# 8_output_sense_mux_half.net
KiCad netlist of a schematic drawn in EAGLE
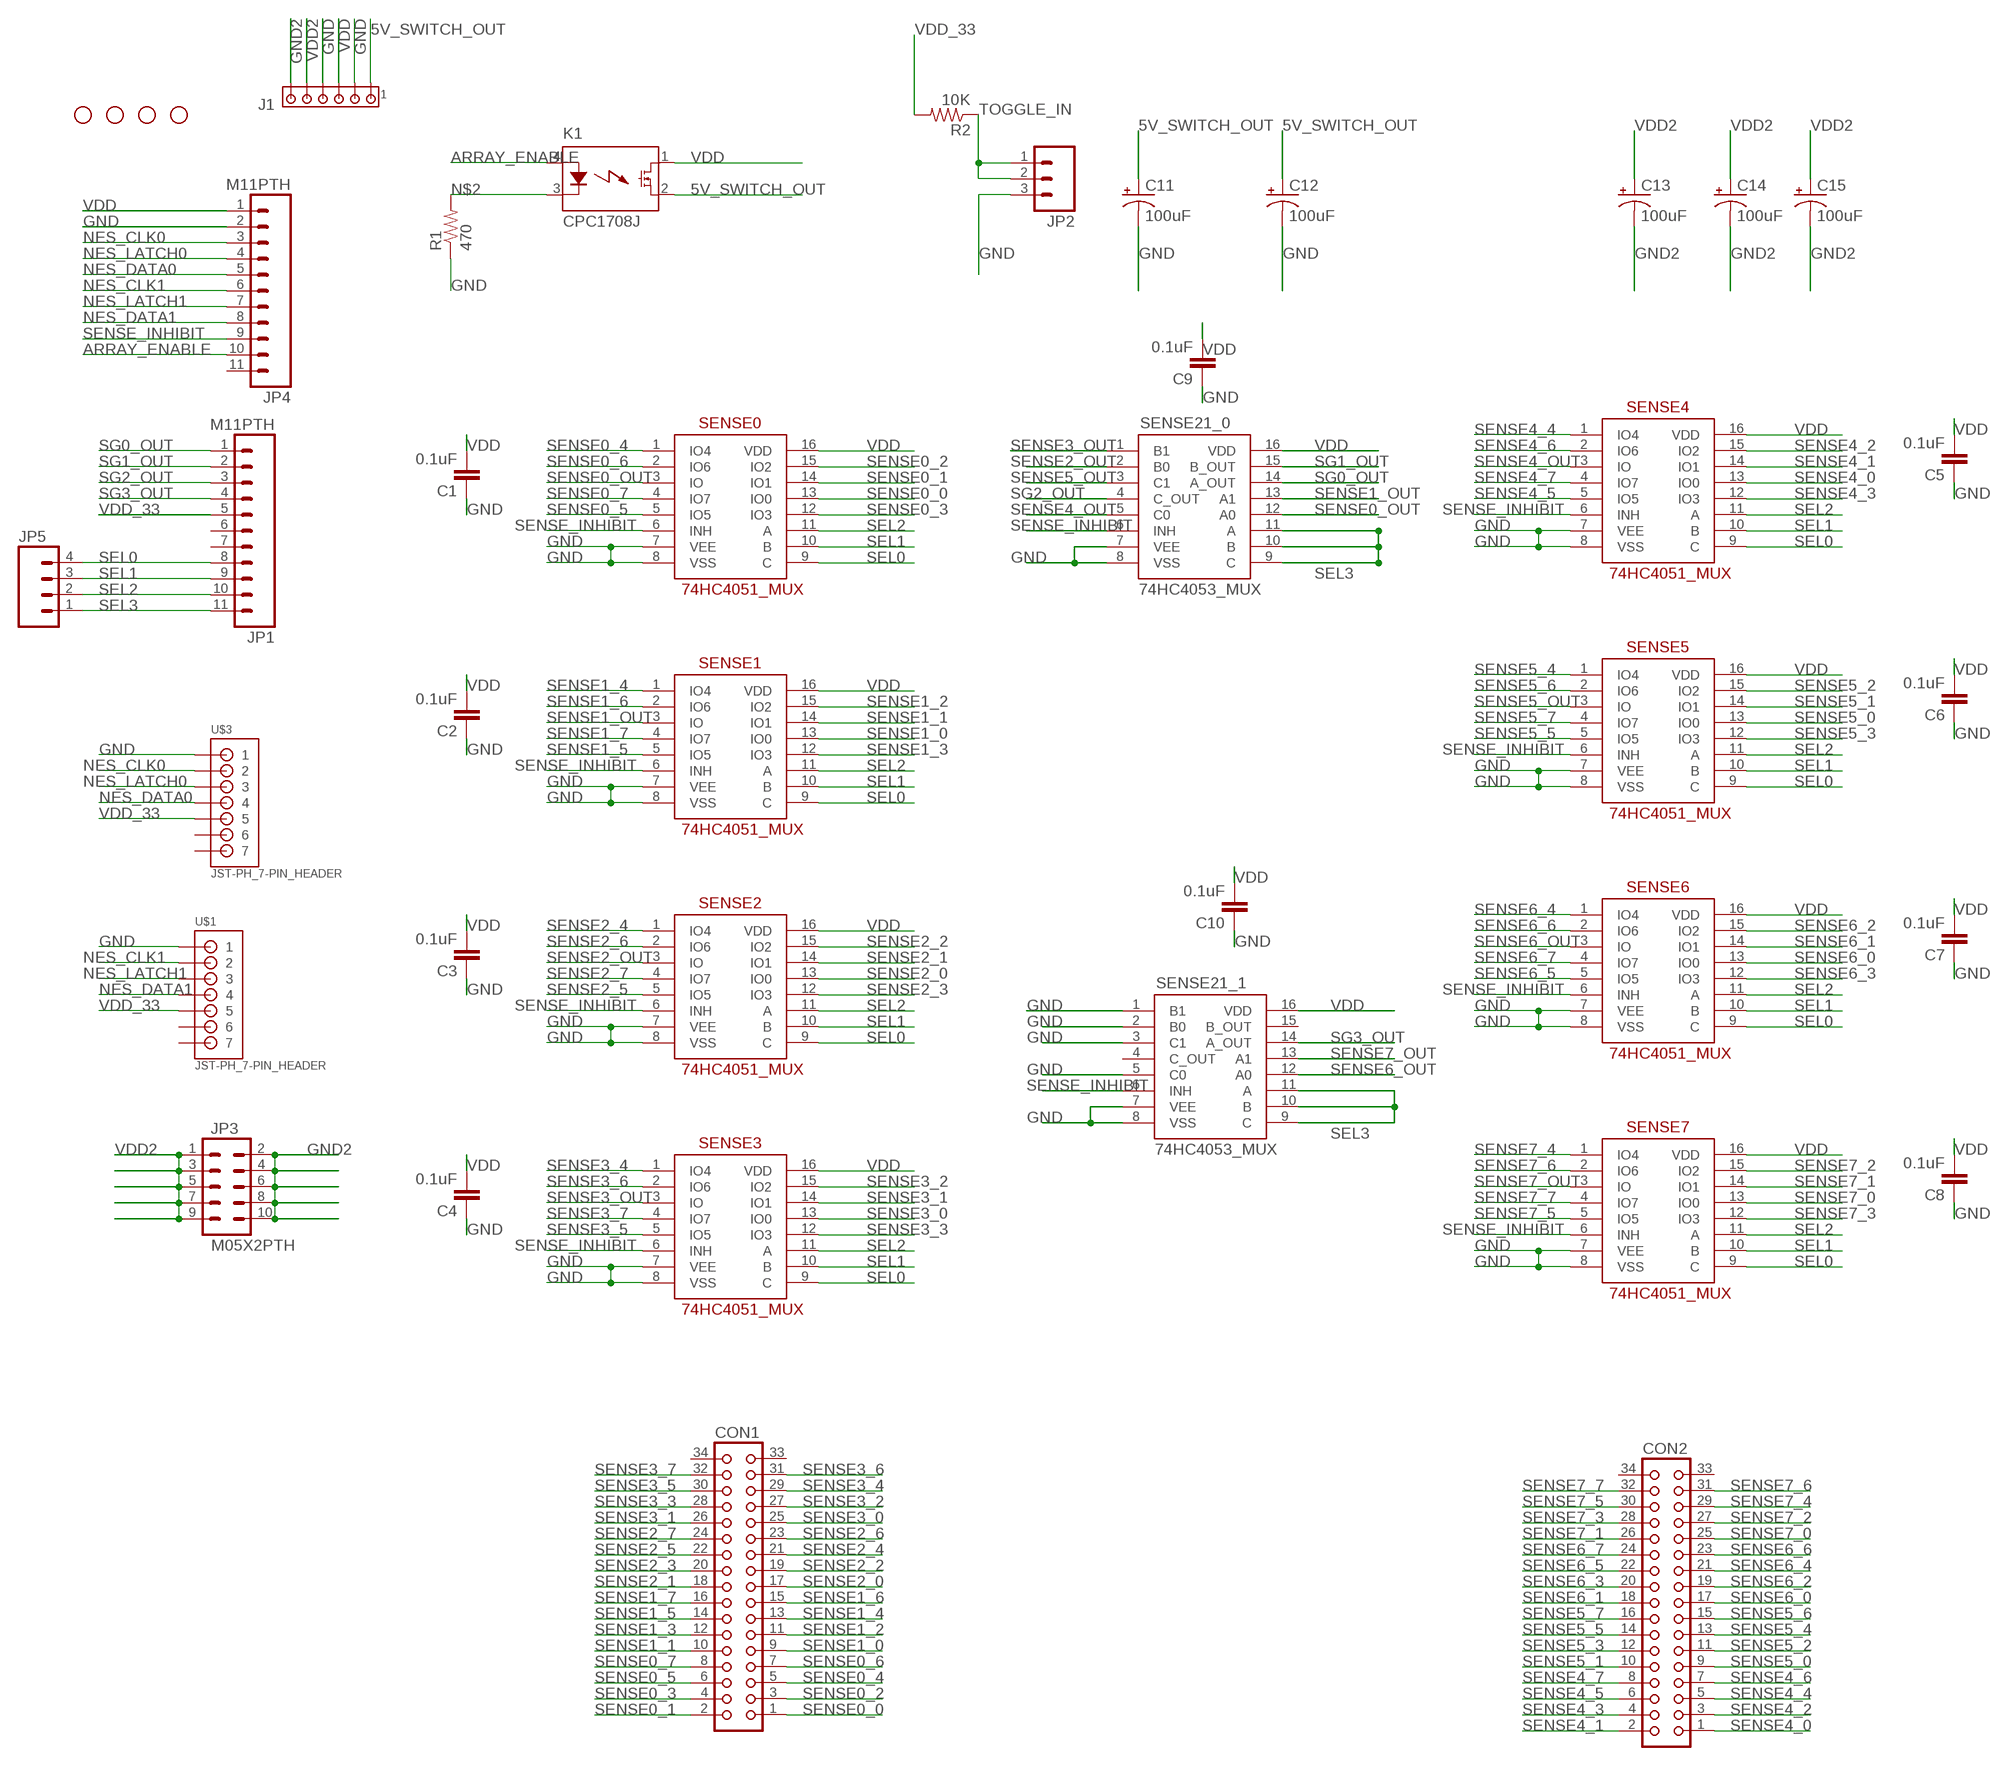
[diagram p0: schematic, sheet 1]

(export (version "E")
  (design (tool "Eeschema 10.0.6"))
  (components
    (comp (ref "C1")
      (value "0.1uF")
      (footprint "eagle-import:C2.5-3")
      (libsource (lib "eagle-import") (part "C2,5-3"))
    )
    (comp (ref "C2")
      (value "0.1uF")
      (footprint "eagle-import:C2.5-3")
      (libsource (lib "eagle-import") (part "C2,5-3"))
    )
    (comp (ref "C3")
      (value "0.1uF")
      (footprint "eagle-import:C2.5-3")
      (libsource (lib "eagle-import") (part "C2,5-3"))
    )
    (comp (ref "C4")
      (value "0.1uF")
      (footprint "eagle-import:C2.5-3")
      (libsource (lib "eagle-import") (part "C2,5-3"))
    )
    (comp (ref "C5")
      (value "0.1uF")
      (footprint "eagle-import:C2.5-3")
      (libsource (lib "eagle-import") (part "C2,5-3"))
    )
    (comp (ref "C6")
      (value "0.1uF")
      (footprint "eagle-import:C2.5-3")
      (libsource (lib "eagle-import") (part "C2,5-3"))
    )
    (comp (ref "C7")
      (value "0.1uF")
      (footprint "eagle-import:C2.5-3")
      (libsource (lib "eagle-import") (part "C2,5-3"))
    )
    (comp (ref "C8")
      (value "0.1uF")
      (footprint "eagle-import:C2.5-3")
      (libsource (lib "eagle-import") (part "C2,5-3"))
    )
    (comp (ref "C9")
      (value "0.1uF")
      (footprint "eagle-import:C2.5-3")
      (libsource (lib "eagle-import") (part "C2,5-3"))
    )
    (comp (ref "C10")
      (value "0.1uF")
      (footprint "eagle-import:C2.5-3")
      (libsource (lib "eagle-import") (part "C2,5-3"))
    )
    (comp (ref "C11")
      (value "100uF")
      (footprint "eagle-import:CPOL-RADIAL-100UF-25V")
      (libsource (lib "eagle-import") (part "CAP_POLPTH1"))
    )
    (comp (ref "C12")
      (value "100uF")
      (footprint "eagle-import:CPOL-RADIAL-100UF-25V")
      (libsource (lib "eagle-import") (part "CAP_POLPTH1"))
    )
    (comp (ref "C13")
      (value "100uF")
      (footprint "eagle-import:CPOL-RADIAL-100UF-25V")
      (libsource (lib "eagle-import") (part "CAP_POLPTH1"))
    )
    (comp (ref "C14")
      (value "100uF")
      (footprint "eagle-import:CPOL-RADIAL-100UF-25V")
      (libsource (lib "eagle-import") (part "CAP_POLPTH1"))
    )
    (comp (ref "C15")
      (value "100uF")
      (footprint "eagle-import:CPOL-RADIAL-100UF-25V")
      (libsource (lib "eagle-import") (part "CAP_POLPTH1"))
    )
    (comp (ref "CON1")
      (value "CON34")
      (footprint "eagle-import:CON34")
      (libsource (lib "eagle-import") (part "CON34"))
    )
    (comp (ref "CON2")
      (value "CON34")
      (footprint "eagle-import:CON34")
      (libsource (lib "eagle-import") (part "CON34"))
    )
    (comp (ref "J1")
      (value "MTA06-156")
      (footprint "eagle-import:1X6MTA")
      (libsource (lib "eagle-import") (part "MTA06-156"))
    )
    (comp (ref "JP1")
      (value "M11PTH")
      (footprint "eagle-import:1X11")
      (libsource (lib "eagle-import") (part "M11PTH"))
    )
    (comp (ref "JP2")
      (value "M03PTH")
      (footprint "eagle-import:1X03")
      (libsource (lib "eagle-import") (part "M03PTH"))
    )
    (comp (ref "JP3")
      (value "M05X2PTH")
      (footprint "eagle-import:AVR_ICSP")
      (libsource (lib "eagle-import") (part "M05X2PTH"))
    )
    (comp (ref "JP4")
      (value "M11PTH")
      (footprint "eagle-import:1X11")
      (libsource (lib "eagle-import") (part "M11PTH"))
    )
    (comp (ref "JP5")
      (value "M04PTH")
      (footprint "eagle-import:1X04")
      (libsource (lib "eagle-import") (part "M04PTH"))
    )
    (comp (ref "K1")
      (value "CPC1708J")
      (footprint "eagle-import:I4-PAC")
      (libsource (lib "eagle-import") (part "CPC1708J"))
    )
    (comp (ref "R1")
      (value "470")
      (footprint "eagle-import:AXIAL-0.3-KIT")
      (libsource (lib "eagle-import") (part "10KOHM1/6W5%(PTH)KIT"))
    )
    (comp (ref "R2")
      (value "10K")
      (footprint "eagle-import:AXIAL-0.3-KIT")
      (libsource (lib "eagle-import") (part "10KOHM1/6W5%(PTH)KIT"))
    )
    (comp (ref "SENSE0")
      (value "74HC4051_MUX")
      (footprint "eagle-import:DIL16")
      (libsource (lib "eagle-import") (part "74HC4051_MUX"))
    )
    (comp (ref "SENSE1")
      (value "74HC4051_MUX")
      (footprint "eagle-import:DIL16")
      (libsource (lib "eagle-import") (part "74HC4051_MUX"))
    )
    (comp (ref "SENSE2")
      (value "74HC4051_MUX")
      (footprint "eagle-import:DIL16")
      (libsource (lib "eagle-import") (part "74HC4051_MUX"))
    )
    (comp (ref "SENSE3")
      (value "74HC4051_MUX")
      (footprint "eagle-import:DIL16")
      (libsource (lib "eagle-import") (part "74HC4051_MUX"))
    )
    (comp (ref "SENSE4")
      (value "74HC4051_MUX")
      (footprint "eagle-import:DIL16")
      (libsource (lib "eagle-import") (part "74HC4051_MUX"))
    )
    (comp (ref "SENSE5")
      (value "74HC4051_MUX")
      (footprint "eagle-import:DIL16")
      (libsource (lib "eagle-import") (part "74HC4051_MUX"))
    )
    (comp (ref "SENSE6")
      (value "74HC4051_MUX")
      (footprint "eagle-import:DIL16")
      (libsource (lib "eagle-import") (part "74HC4051_MUX"))
    )
    (comp (ref "SENSE7")
      (value "74HC4051_MUX")
      (footprint "eagle-import:DIL16")
      (libsource (lib "eagle-import") (part "74HC4051_MUX"))
    )
    (comp (ref "SENSE21_0")
      (value "74HC4053_MUX")
      (footprint "eagle-import:DIL16")
      (libsource (lib "eagle-import") (part "74HC4053_MUX"))
    )
    (comp (ref "SENSE21_1")
      (value "74HC4053_MUX")
      (footprint "eagle-import:DIL16")
      (libsource (lib "eagle-import") (part "74HC4053_MUX"))
    )
    (comp (ref "STANDOFF1")
      (value "STAND-OFF")
      (footprint "eagle-import:STAND-OFF")
      (libsource (lib "eagle-import") (part "STAND-OFF"))
    )
    (comp (ref "STANDOFF2")
      (value "STAND-OFF")
      (footprint "eagle-import:STAND-OFF")
      (libsource (lib "eagle-import") (part "STAND-OFF"))
    )
    (comp (ref "STANDOFF3")
      (value "STAND-OFF")
      (footprint "eagle-import:STAND-OFF")
      (libsource (lib "eagle-import") (part "STAND-OFF"))
    )
    (comp (ref "STANDOFF4")
      (value "STAND-OFF")
      (footprint "eagle-import:STAND-OFF")
      (libsource (lib "eagle-import") (part "STAND-OFF"))
    )
    (comp (ref "U$1")
      (value "JST-PH_7-PIN_HEADER")
      (footprint "eagle-import:JST_B7B-PH_HEADER")
      (libsource (lib "eagle-import") (part "JST-PH_7-PIN_HEADER"))
    )
    (comp (ref "U$3")
      (value "JST-PH_7-PIN_HEADER")
      (footprint "eagle-import:JST_B7B-PH_HEADER")
      (libsource (lib "eagle-import") (part "JST-PH_7-PIN_HEADER"))
    )
  )
  (nets
    (net (code "1") (name "/5V_SWITCH_OUT") (class "Default")
      (node (ref "C11") (pin "1") (pinfunction "+_1") (pintype "passive"))
      (node (ref "C12") (pin "1") (pinfunction "+_1") (pintype "passive"))
      (node (ref "J1") (pin "1") (pinfunction "1_1") (pintype "passive"))
      (node (ref "K1") (pin "2") (pinfunction "DS2_2") (pintype "passive"))
    )
    (net (code "2") (name "/ARRAY_ENABLE") (class "Default")
      (node (ref "JP4") (pin "10") (pinfunction "10_10") (pintype "passive"))
      (node (ref "K1") (pin "4") (pinfunction "A_4") (pintype "passive"))
    )
    (net (code "3") (name "/GND") (class "Default")
      (node (ref "C1") (pin "1") (pinfunction "1_1") (pintype "passive"))
      (node (ref "C10") (pin "1") (pinfunction "1_1") (pintype "passive"))
      (node (ref "C11") (pin "2") (pinfunction "-_2") (pintype "passive"))
      (node (ref "C12") (pin "2") (pinfunction "-_2") (pintype "passive"))
      (node (ref "C2") (pin "1") (pinfunction "1_1") (pintype "passive"))
      (node (ref "C3") (pin "1") (pinfunction "1_1") (pintype "passive"))
      (node (ref "C4") (pin "1") (pinfunction "1_1") (pintype "passive"))
      (node (ref "C5") (pin "1") (pinfunction "1_1") (pintype "passive"))
      (node (ref "C6") (pin "1") (pinfunction "1_1") (pintype "passive"))
      (node (ref "C7") (pin "1") (pinfunction "1_1") (pintype "passive"))
      (node (ref "C8") (pin "1") (pinfunction "1_1") (pintype "passive"))
      (node (ref "C9") (pin "1") (pinfunction "1_1") (pintype "passive"))
      (node (ref "J1") (pin "2") (pinfunction "2_2") (pintype "passive"))
      (node (ref "J1") (pin "4") (pinfunction "4_4") (pintype "passive"))
      (node (ref "JP2") (pin "3") (pinfunction "3_3") (pintype "passive"))
      (node (ref "JP4") (pin "2") (pinfunction "2_2") (pintype "passive"))
      (node (ref "R1") (pin "P$1") (pinfunction "1_P$1") (pintype "passive"))
      (node (ref "SENSE0") (pin "7") (pinfunction "VEE_7") (pintype "bidirectional"))
      (node (ref "SENSE0") (pin "8") (pinfunction "VSS_8") (pintype "bidirectional"))
      (node (ref "SENSE1") (pin "7") (pinfunction "VEE_7") (pintype "bidirectional"))
      (node (ref "SENSE1") (pin "8") (pinfunction "VSS_8") (pintype "bidirectional"))
      (node (ref "SENSE2") (pin "7") (pinfunction "VEE_7") (pintype "bidirectional"))
      (node (ref "SENSE2") (pin "8") (pinfunction "VSS_8") (pintype "bidirectional"))
      (node (ref "SENSE21_0") (pin "7") (pinfunction "VEE_7") (pintype "bidirectional"))
      (node (ref "SENSE21_0") (pin "8") (pinfunction "VSS_8") (pintype "bidirectional"))
      (node (ref "SENSE21_1") (pin "1") (pinfunction "B1_1") (pintype "bidirectional"))
      (node (ref "SENSE21_1") (pin "2") (pinfunction "B0_2") (pintype "bidirectional"))
      (node (ref "SENSE21_1") (pin "3") (pinfunction "C1_3") (pintype "bidirectional"))
      (node (ref "SENSE21_1") (pin "5") (pinfunction "C0_5") (pintype "bidirectional"))
      (node (ref "SENSE21_1") (pin "7") (pinfunction "VEE_7") (pintype "bidirectional"))
      (node (ref "SENSE21_1") (pin "8") (pinfunction "VSS_8") (pintype "bidirectional"))
      (node (ref "SENSE3") (pin "7") (pinfunction "VEE_7") (pintype "bidirectional"))
      (node (ref "SENSE3") (pin "8") (pinfunction "VSS_8") (pintype "bidirectional"))
      (node (ref "SENSE4") (pin "7") (pinfunction "VEE_7") (pintype "bidirectional"))
      (node (ref "SENSE4") (pin "8") (pinfunction "VSS_8") (pintype "bidirectional"))
      (node (ref "SENSE5") (pin "7") (pinfunction "VEE_7") (pintype "bidirectional"))
      (node (ref "SENSE5") (pin "8") (pinfunction "VSS_8") (pintype "bidirectional"))
      (node (ref "SENSE6") (pin "7") (pinfunction "VEE_7") (pintype "bidirectional"))
      (node (ref "SENSE6") (pin "8") (pinfunction "VSS_8") (pintype "bidirectional"))
      (node (ref "SENSE7") (pin "7") (pinfunction "VEE_7") (pintype "bidirectional"))
      (node (ref "SENSE7") (pin "8") (pinfunction "VSS_8") (pintype "bidirectional"))
      (node (ref "U$1") (pin "P1") (pinfunction "1_P1") (pintype "bidirectional"))
      (node (ref "U$3") (pin "P1") (pinfunction "1_P1") (pintype "bidirectional"))
    )
    (net (code "4") (name "/GND2") (class "Default")
      (node (ref "C13") (pin "2") (pinfunction "-_2") (pintype "passive"))
      (node (ref "C14") (pin "2") (pinfunction "-_2") (pintype "passive"))
      (node (ref "C15") (pin "2") (pinfunction "-_2") (pintype "passive"))
      (node (ref "J1") (pin "6") (pinfunction "6_6") (pintype "passive"))
      (node (ref "JP3") (pin "10") (pinfunction "10_10") (pintype "passive"))
      (node (ref "JP3") (pin "2") (pinfunction "2_2") (pintype "passive"))
      (node (ref "JP3") (pin "4") (pinfunction "4_4") (pintype "passive"))
      (node (ref "JP3") (pin "6") (pinfunction "6_6") (pintype "passive"))
      (node (ref "JP3") (pin "8") (pinfunction "8_8") (pintype "passive"))
    )
    (net (code "5") (name "/N$2") (class "Default")
      (node (ref "K1") (pin "3") (pinfunction "K_3") (pintype "passive"))
      (node (ref "R1") (pin "P$2") (pinfunction "2_P$2") (pintype "passive"))
    )
    (net (code "6") (name "/NES_CLK0") (class "Default")
      (node (ref "JP4") (pin "3") (pinfunction "3_3") (pintype "passive"))
      (node (ref "U$3") (pin "P2") (pinfunction "2_P2") (pintype "bidirectional"))
    )
    (net (code "7") (name "/NES_CLK1") (class "Default")
      (node (ref "JP4") (pin "6") (pinfunction "6_6") (pintype "passive"))
      (node (ref "U$1") (pin "P2") (pinfunction "2_P2") (pintype "bidirectional"))
    )
    (net (code "8") (name "/NES_DATA0") (class "Default")
      (node (ref "JP4") (pin "5") (pinfunction "5_5") (pintype "passive"))
      (node (ref "U$3") (pin "P4") (pinfunction "4_P4") (pintype "bidirectional"))
    )
    (net (code "9") (name "/NES_DATA1") (class "Default")
      (node (ref "JP4") (pin "8") (pinfunction "8_8") (pintype "passive"))
      (node (ref "U$1") (pin "P4") (pinfunction "4_P4") (pintype "bidirectional"))
    )
    (net (code "10") (name "/NES_LATCH0") (class "Default")
      (node (ref "JP4") (pin "4") (pinfunction "4_4") (pintype "passive"))
      (node (ref "U$3") (pin "P3") (pinfunction "3_P3") (pintype "bidirectional"))
    )
    (net (code "11") (name "/NES_LATCH1") (class "Default")
      (node (ref "JP4") (pin "7") (pinfunction "7_7") (pintype "passive"))
      (node (ref "U$1") (pin "P3") (pinfunction "3_P3") (pintype "bidirectional"))
    )
    (net (code "12") (name "/SEL0") (class "Default")
      (node (ref "JP1") (pin "8") (pinfunction "8_8") (pintype "passive"))
      (node (ref "JP5") (pin "4") (pinfunction "4_4") (pintype "passive"))
      (node (ref "SENSE0") (pin "9") (pinfunction "C_9") (pintype "bidirectional"))
      (node (ref "SENSE1") (pin "9") (pinfunction "C_9") (pintype "bidirectional"))
      (node (ref "SENSE2") (pin "9") (pinfunction "C_9") (pintype "bidirectional"))
      (node (ref "SENSE3") (pin "9") (pinfunction "C_9") (pintype "bidirectional"))
      (node (ref "SENSE4") (pin "9") (pinfunction "C_9") (pintype "bidirectional"))
      (node (ref "SENSE5") (pin "9") (pinfunction "C_9") (pintype "bidirectional"))
      (node (ref "SENSE6") (pin "9") (pinfunction "C_9") (pintype "bidirectional"))
      (node (ref "SENSE7") (pin "9") (pinfunction "C_9") (pintype "bidirectional"))
    )
    (net (code "13") (name "/SEL1") (class "Default")
      (node (ref "JP1") (pin "9") (pinfunction "9_9") (pintype "passive"))
      (node (ref "JP5") (pin "3") (pinfunction "3_3") (pintype "passive"))
      (node (ref "SENSE0") (pin "10") (pinfunction "B_10") (pintype "bidirectional"))
      (node (ref "SENSE1") (pin "10") (pinfunction "B_10") (pintype "bidirectional"))
      (node (ref "SENSE2") (pin "10") (pinfunction "B_10") (pintype "bidirectional"))
      (node (ref "SENSE3") (pin "10") (pinfunction "B_10") (pintype "bidirectional"))
      (node (ref "SENSE4") (pin "10") (pinfunction "B_10") (pintype "bidirectional"))
      (node (ref "SENSE5") (pin "10") (pinfunction "B_10") (pintype "bidirectional"))
      (node (ref "SENSE6") (pin "10") (pinfunction "B_10") (pintype "bidirectional"))
      (node (ref "SENSE7") (pin "10") (pinfunction "B_10") (pintype "bidirectional"))
    )
    (net (code "14") (name "/SEL2") (class "Default")
      (node (ref "JP1") (pin "10") (pinfunction "10_10") (pintype "passive"))
      (node (ref "JP5") (pin "2") (pinfunction "2_2") (pintype "passive"))
      (node (ref "SENSE0") (pin "11") (pinfunction "A_11") (pintype "bidirectional"))
      (node (ref "SENSE1") (pin "11") (pinfunction "A_11") (pintype "bidirectional"))
      (node (ref "SENSE2") (pin "11") (pinfunction "A_11") (pintype "bidirectional"))
      (node (ref "SENSE3") (pin "11") (pinfunction "A_11") (pintype "bidirectional"))
      (node (ref "SENSE4") (pin "11") (pinfunction "A_11") (pintype "bidirectional"))
      (node (ref "SENSE5") (pin "11") (pinfunction "A_11") (pintype "bidirectional"))
      (node (ref "SENSE6") (pin "11") (pinfunction "A_11") (pintype "bidirectional"))
      (node (ref "SENSE7") (pin "11") (pinfunction "A_11") (pintype "bidirectional"))
    )
    (net (code "15") (name "/SEL3") (class "Default")
      (node (ref "JP1") (pin "11") (pinfunction "11_11") (pintype "passive"))
      (node (ref "JP5") (pin "1") (pinfunction "1_1") (pintype "passive"))
      (node (ref "SENSE21_0") (pin "10") (pinfunction "B_10") (pintype "bidirectional"))
      (node (ref "SENSE21_0") (pin "11") (pinfunction "A_11") (pintype "bidirectional"))
      (node (ref "SENSE21_0") (pin "9") (pinfunction "C_9") (pintype "bidirectional"))
      (node (ref "SENSE21_1") (pin "10") (pinfunction "B_10") (pintype "bidirectional"))
      (node (ref "SENSE21_1") (pin "11") (pinfunction "A_11") (pintype "bidirectional"))
      (node (ref "SENSE21_1") (pin "9") (pinfunction "C_9") (pintype "bidirectional"))
    )
    (net (code "16") (name "/SENSE0_0") (class "Default")
      (node (ref "CON1") (pin "1") (pinfunction "1_1") (pintype "passive"))
      (node (ref "SENSE0") (pin "13") (pinfunction "IO0_13") (pintype "bidirectional"))
    )
    (net (code "17") (name "/SENSE0_1") (class "Default")
      (node (ref "CON1") (pin "2") (pinfunction "2_2") (pintype "passive"))
      (node (ref "SENSE0") (pin "14") (pinfunction "IO1_14") (pintype "bidirectional"))
    )
    (net (code "18") (name "/SENSE0_2") (class "Default")
      (node (ref "CON1") (pin "3") (pinfunction "3_3") (pintype "passive"))
      (node (ref "SENSE0") (pin "15") (pinfunction "IO2_15") (pintype "bidirectional"))
    )
    (net (code "19") (name "/SENSE0_3") (class "Default")
      (node (ref "CON1") (pin "4") (pinfunction "4_4") (pintype "passive"))
      (node (ref "SENSE0") (pin "12") (pinfunction "IO3_12") (pintype "bidirectional"))
    )
    (net (code "20") (name "/SENSE0_4") (class "Default")
      (node (ref "CON1") (pin "5") (pinfunction "5_5") (pintype "passive"))
      (node (ref "SENSE0") (pin "1") (pinfunction "IO4_1") (pintype "bidirectional"))
    )
    (net (code "21") (name "/SENSE0_5") (class "Default")
      (node (ref "CON1") (pin "6") (pinfunction "6_6") (pintype "passive"))
      (node (ref "SENSE0") (pin "5") (pinfunction "IO5_5") (pintype "bidirectional"))
    )
    (net (code "22") (name "/SENSE0_6") (class "Default")
      (node (ref "CON1") (pin "7") (pinfunction "7_7") (pintype "passive"))
      (node (ref "SENSE0") (pin "2") (pinfunction "IO6_2") (pintype "bidirectional"))
    )
    (net (code "23") (name "/SENSE0_7") (class "Default")
      (node (ref "CON1") (pin "8") (pinfunction "8_8") (pintype "passive"))
      (node (ref "SENSE0") (pin "4") (pinfunction "IO7_4") (pintype "bidirectional"))
    )
    (net (code "24") (name "/SENSE0_OUT") (class "Default")
      (node (ref "SENSE0") (pin "3") (pinfunction "IO_3") (pintype "bidirectional"))
      (node (ref "SENSE21_0") (pin "12") (pinfunction "A0_12") (pintype "bidirectional"))
    )
    (net (code "25") (name "/SENSE1_0") (class "Default")
      (node (ref "CON1") (pin "9") (pinfunction "9_9") (pintype "passive"))
      (node (ref "SENSE1") (pin "13") (pinfunction "IO0_13") (pintype "bidirectional"))
    )
    (net (code "26") (name "/SENSE1_1") (class "Default")
      (node (ref "CON1") (pin "10") (pinfunction "10_10") (pintype "passive"))
      (node (ref "SENSE1") (pin "14") (pinfunction "IO1_14") (pintype "bidirectional"))
    )
    (net (code "27") (name "/SENSE1_2") (class "Default")
      (node (ref "CON1") (pin "11") (pinfunction "11_11") (pintype "passive"))
      (node (ref "SENSE1") (pin "15") (pinfunction "IO2_15") (pintype "bidirectional"))
    )
    (net (code "28") (name "/SENSE1_3") (class "Default")
      (node (ref "CON1") (pin "12") (pinfunction "12_12") (pintype "passive"))
      (node (ref "SENSE1") (pin "12") (pinfunction "IO3_12") (pintype "bidirectional"))
    )
    (net (code "29") (name "/SENSE1_4") (class "Default")
      (node (ref "CON1") (pin "13") (pinfunction "13_13") (pintype "passive"))
      (node (ref "SENSE1") (pin "1") (pinfunction "IO4_1") (pintype "bidirectional"))
    )
    (net (code "30") (name "/SENSE1_5") (class "Default")
      (node (ref "CON1") (pin "14") (pinfunction "14_14") (pintype "passive"))
      (node (ref "SENSE1") (pin "5") (pinfunction "IO5_5") (pintype "bidirectional"))
    )
    (net (code "31") (name "/SENSE1_6") (class "Default")
      (node (ref "CON1") (pin "15") (pinfunction "15_15") (pintype "passive"))
      (node (ref "SENSE1") (pin "2") (pinfunction "IO6_2") (pintype "bidirectional"))
    )
    (net (code "32") (name "/SENSE1_7") (class "Default")
      (node (ref "CON1") (pin "16") (pinfunction "16_16") (pintype "passive"))
      (node (ref "SENSE1") (pin "4") (pinfunction "IO7_4") (pintype "bidirectional"))
    )
    (net (code "33") (name "/SENSE1_OUT") (class "Default")
      (node (ref "SENSE1") (pin "3") (pinfunction "IO_3") (pintype "bidirectional"))
      (node (ref "SENSE21_0") (pin "13") (pinfunction "A1_13") (pintype "bidirectional"))
    )
    (net (code "34") (name "/SENSE2_0") (class "Default")
      (node (ref "CON1") (pin "17") (pinfunction "17_17") (pintype "passive"))
      (node (ref "SENSE2") (pin "13") (pinfunction "IO0_13") (pintype "bidirectional"))
    )
    (net (code "35") (name "/SENSE2_1") (class "Default")
      (node (ref "CON1") (pin "18") (pinfunction "18_18") (pintype "passive"))
      (node (ref "SENSE2") (pin "14") (pinfunction "IO1_14") (pintype "bidirectional"))
    )
    (net (code "36") (name "/SENSE2_2") (class "Default")
      (node (ref "CON1") (pin "19") (pinfunction "19_19") (pintype "passive"))
      (node (ref "SENSE2") (pin "15") (pinfunction "IO2_15") (pintype "bidirectional"))
    )
    (net (code "37") (name "/SENSE2_3") (class "Default")
      (node (ref "CON1") (pin "20") (pinfunction "20_20") (pintype "passive"))
      (node (ref "SENSE2") (pin "12") (pinfunction "IO3_12") (pintype "bidirectional"))
    )
    (net (code "38") (name "/SENSE2_4") (class "Default")
      (node (ref "CON1") (pin "21") (pinfunction "21_21") (pintype "passive"))
      (node (ref "SENSE2") (pin "1") (pinfunction "IO4_1") (pintype "bidirectional"))
    )
    (net (code "39") (name "/SENSE2_5") (class "Default")
      (node (ref "CON1") (pin "22") (pinfunction "22_22") (pintype "passive"))
      (node (ref "SENSE2") (pin "5") (pinfunction "IO5_5") (pintype "bidirectional"))
    )
    (net (code "40") (name "/SENSE2_6") (class "Default")
      (node (ref "CON1") (pin "23") (pinfunction "23_23") (pintype "passive"))
      (node (ref "SENSE2") (pin "2") (pinfunction "IO6_2") (pintype "bidirectional"))
    )
    (net (code "41") (name "/SENSE2_7") (class "Default")
      (node (ref "CON1") (pin "24") (pinfunction "24_24") (pintype "passive"))
      (node (ref "SENSE2") (pin "4") (pinfunction "IO7_4") (pintype "bidirectional"))
    )
    (net (code "42") (name "/SENSE2_OUT") (class "Default")
      (node (ref "SENSE2") (pin "3") (pinfunction "IO_3") (pintype "bidirectional"))
      (node (ref "SENSE21_0") (pin "2") (pinfunction "B0_2") (pintype "bidirectional"))
    )
    (net (code "43") (name "/SENSE3_0") (class "Default")
      (node (ref "CON1") (pin "25") (pinfunction "25_25") (pintype "passive"))
      (node (ref "SENSE3") (pin "13") (pinfunction "IO0_13") (pintype "bidirectional"))
    )
    (net (code "44") (name "/SENSE3_1") (class "Default")
      (node (ref "CON1") (pin "26") (pinfunction "26_26") (pintype "passive"))
      (node (ref "SENSE3") (pin "14") (pinfunction "IO1_14") (pintype "bidirectional"))
    )
    (net (code "45") (name "/SENSE3_2") (class "Default")
      (node (ref "CON1") (pin "27") (pinfunction "27_27") (pintype "passive"))
      (node (ref "SENSE3") (pin "15") (pinfunction "IO2_15") (pintype "bidirectional"))
    )
    (net (code "46") (name "/SENSE3_3") (class "Default")
      (node (ref "CON1") (pin "28") (pinfunction "28_28") (pintype "passive"))
      (node (ref "SENSE3") (pin "12") (pinfunction "IO3_12") (pintype "bidirectional"))
    )
    (net (code "47") (name "/SENSE3_4") (class "Default")
      (node (ref "CON1") (pin "29") (pinfunction "29_29") (pintype "passive"))
      (node (ref "SENSE3") (pin "1") (pinfunction "IO4_1") (pintype "bidirectional"))
    )
    (net (code "48") (name "/SENSE3_5") (class "Default")
      (node (ref "CON1") (pin "30") (pinfunction "30_30") (pintype "passive"))
      (node (ref "SENSE3") (pin "5") (pinfunction "IO5_5") (pintype "bidirectional"))
    )
    (net (code "49") (name "/SENSE3_6") (class "Default")
      (node (ref "CON1") (pin "31") (pinfunction "31_31") (pintype "passive"))
      (node (ref "SENSE3") (pin "2") (pinfunction "IO6_2") (pintype "bidirectional"))
    )
    (net (code "50") (name "/SENSE3_7") (class "Default")
      (node (ref "CON1") (pin "32") (pinfunction "32_32") (pintype "passive"))
      (node (ref "SENSE3") (pin "4") (pinfunction "IO7_4") (pintype "bidirectional"))
    )
    (net (code "51") (name "/SENSE3_OUT") (class "Default")
      (node (ref "SENSE21_0") (pin "1") (pinfunction "B1_1") (pintype "bidirectional"))
      (node (ref "SENSE3") (pin "3") (pinfunction "IO_3") (pintype "bidirectional"))
    )
    (net (code "52") (name "/SENSE4_0") (class "Default")
      (node (ref "CON2") (pin "1") (pinfunction "1_1") (pintype "passive"))
      (node (ref "SENSE4") (pin "13") (pinfunction "IO0_13") (pintype "bidirectional"))
    )
    (net (code "53") (name "/SENSE4_1") (class "Default")
      (node (ref "CON2") (pin "2") (pinfunction "2_2") (pintype "passive"))
      (node (ref "SENSE4") (pin "14") (pinfunction "IO1_14") (pintype "bidirectional"))
    )
    (net (code "54") (name "/SENSE4_2") (class "Default")
      (node (ref "CON2") (pin "3") (pinfunction "3_3") (pintype "passive"))
      (node (ref "SENSE4") (pin "15") (pinfunction "IO2_15") (pintype "bidirectional"))
    )
    (net (code "55") (name "/SENSE4_3") (class "Default")
      (node (ref "CON2") (pin "4") (pinfunction "4_4") (pintype "passive"))
      (node (ref "SENSE4") (pin "12") (pinfunction "IO3_12") (pintype "bidirectional"))
    )
    (net (code "56") (name "/SENSE4_4") (class "Default")
      (node (ref "CON2") (pin "5") (pinfunction "5_5") (pintype "passive"))
      (node (ref "SENSE4") (pin "1") (pinfunction "IO4_1") (pintype "bidirectional"))
    )
    (net (code "57") (name "/SENSE4_5") (class "Default")
      (node (ref "CON2") (pin "6") (pinfunction "6_6") (pintype "passive"))
      (node (ref "SENSE4") (pin "5") (pinfunction "IO5_5") (pintype "bidirectional"))
    )
    (net (code "58") (name "/SENSE4_6") (class "Default")
      (node (ref "CON2") (pin "7") (pinfunction "7_7") (pintype "passive"))
      (node (ref "SENSE4") (pin "2") (pinfunction "IO6_2") (pintype "bidirectional"))
    )
    (net (code "59") (name "/SENSE4_7") (class "Default")
      (node (ref "CON2") (pin "8") (pinfunction "8_8") (pintype "passive"))
      (node (ref "SENSE4") (pin "4") (pinfunction "IO7_4") (pintype "bidirectional"))
    )
    (net (code "60") (name "/SENSE4_OUT") (class "Default")
      (node (ref "SENSE21_0") (pin "5") (pinfunction "C0_5") (pintype "bidirectional"))
      (node (ref "SENSE4") (pin "3") (pinfunction "IO_3") (pintype "bidirectional"))
    )
    (net (code "61") (name "/SENSE5_0") (class "Default")
      (node (ref "CON2") (pin "9") (pinfunction "9_9") (pintype "passive"))
      (node (ref "SENSE5") (pin "13") (pinfunction "IO0_13") (pintype "bidirectional"))
    )
    (net (code "62") (name "/SENSE5_1") (class "Default")
      (node (ref "CON2") (pin "10") (pinfunction "10_10") (pintype "passive"))
      (node (ref "SENSE5") (pin "14") (pinfunction "IO1_14") (pintype "bidirectional"))
    )
    (net (code "63") (name "/SENSE5_2") (class "Default")
      (node (ref "CON2") (pin "11") (pinfunction "11_11") (pintype "passive"))
      (node (ref "SENSE5") (pin "15") (pinfunction "IO2_15") (pintype "bidirectional"))
    )
    (net (code "64") (name "/SENSE5_3") (class "Default")
      (node (ref "CON2") (pin "12") (pinfunction "12_12") (pintype "passive"))
      (node (ref "SENSE5") (pin "12") (pinfunction "IO3_12") (pintype "bidirectional"))
    )
    (net (code "65") (name "/SENSE5_4") (class "Default")
      (node (ref "CON2") (pin "13") (pinfunction "13_13") (pintype "passive"))
      (node (ref "SENSE5") (pin "1") (pinfunction "IO4_1") (pintype "bidirectional"))
    )
    (net (code "66") (name "/SENSE5_5") (class "Default")
      (node (ref "CON2") (pin "14") (pinfunction "14_14") (pintype "passive"))
      (node (ref "SENSE5") (pin "5") (pinfunction "IO5_5") (pintype "bidirectional"))
    )
    (net (code "67") (name "/SENSE5_6") (class "Default")
      (node (ref "CON2") (pin "15") (pinfunction "15_15") (pintype "passive"))
      (node (ref "SENSE5") (pin "2") (pinfunction "IO6_2") (pintype "bidirectional"))
    )
    (net (code "68") (name "/SENSE5_7") (class "Default")
      (node (ref "CON2") (pin "16") (pinfunction "16_16") (pintype "passive"))
      (node (ref "SENSE5") (pin "4") (pinfunction "IO7_4") (pintype "bidirectional"))
    )
    (net (code "69") (name "/SENSE5_OUT") (class "Default")
      (node (ref "SENSE21_0") (pin "3") (pinfunction "C1_3") (pintype "bidirectional"))
      (node (ref "SENSE5") (pin "3") (pinfunction "IO_3") (pintype "bidirectional"))
    )
    (net (code "70") (name "/SENSE6_0") (class "Default")
      (node (ref "CON2") (pin "17") (pinfunction "17_17") (pintype "passive"))
      (node (ref "SENSE6") (pin "13") (pinfunction "IO0_13") (pintype "bidirectional"))
    )
    (net (code "71") (name "/SENSE6_1") (class "Default")
      (node (ref "CON2") (pin "18") (pinfunction "18_18") (pintype "passive"))
      (node (ref "SENSE6") (pin "14") (pinfunction "IO1_14") (pintype "bidirectional"))
    )
    (net (code "72") (name "/SENSE6_2") (class "Default")
      (node (ref "CON2") (pin "19") (pinfunction "19_19") (pintype "passive"))
      (node (ref "SENSE6") (pin "15") (pinfunction "IO2_15") (pintype "bidirectional"))
    )
    (net (code "73") (name "/SENSE6_3") (class "Default")
      (node (ref "CON2") (pin "20") (pinfunction "20_20") (pintype "passive"))
      (node (ref "SENSE6") (pin "12") (pinfunction "IO3_12") (pintype "bidirectional"))
    )
    (net (code "74") (name "/SENSE6_4") (class "Default")
      (node (ref "CON2") (pin "21") (pinfunction "21_21") (pintype "passive"))
      (node (ref "SENSE6") (pin "1") (pinfunction "IO4_1") (pintype "bidirectional"))
    )
    (net (code "75") (name "/SENSE6_5") (class "Default")
      (node (ref "CON2") (pin "22") (pinfunction "22_22") (pintype "passive"))
      (node (ref "SENSE6") (pin "5") (pinfunction "IO5_5") (pintype "bidirectional"))
    )
    (net (code "76") (name "/SENSE6_6") (class "Default")
      (node (ref "CON2") (pin "23") (pinfunction "23_23") (pintype "passive"))
      (node (ref "SENSE6") (pin "2") (pinfunction "IO6_2") (pintype "bidirectional"))
    )
    (net (code "77") (name "/SENSE6_7") (class "Default")
      (node (ref "CON2") (pin "24") (pinfunction "24_24") (pintype "passive"))
      (node (ref "SENSE6") (pin "4") (pinfunction "IO7_4") (pintype "bidirectional"))
    )
    (net (code "78") (name "/SENSE6_OUT") (class "Default")
      (node (ref "SENSE21_1") (pin "12") (pinfunction "A0_12") (pintype "bidirectional"))
      (node (ref "SENSE6") (pin "3") (pinfunction "IO_3") (pintype "bidirectional"))
    )
    (net (code "79") (name "/SENSE7_0") (class "Default")
      (node (ref "CON2") (pin "25") (pinfunction "25_25") (pintype "passive"))
      (node (ref "SENSE7") (pin "13") (pinfunction "IO0_13") (pintype "bidirectional"))
    )
    (net (code "80") (name "/SENSE7_1") (class "Default")
      (node (ref "CON2") (pin "26") (pinfunction "26_26") (pintype "passive"))
      (node (ref "SENSE7") (pin "14") (pinfunction "IO1_14") (pintype "bidirectional"))
    )
    (net (code "81") (name "/SENSE7_2") (class "Default")
      (node (ref "CON2") (pin "27") (pinfunction "27_27") (pintype "passive"))
      (node (ref "SENSE7") (pin "15") (pinfunction "IO2_15") (pintype "bidirectional"))
    )
    (net (code "82") (name "/SENSE7_3") (class "Default")
      (node (ref "CON2") (pin "28") (pinfunction "28_28") (pintype "passive"))
      (node (ref "SENSE7") (pin "12") (pinfunction "IO3_12") (pintype "bidirectional"))
    )
    (net (code "83") (name "/SENSE7_4") (class "Default")
      (node (ref "CON2") (pin "29") (pinfunction "29_29") (pintype "passive"))
      (node (ref "SENSE7") (pin "1") (pinfunction "IO4_1") (pintype "bidirectional"))
    )
    (net (code "84") (name "/SENSE7_5") (class "Default")
      (node (ref "CON2") (pin "30") (pinfunction "30_30") (pintype "passive"))
      (node (ref "SENSE7") (pin "5") (pinfunction "IO5_5") (pintype "bidirectional"))
    )
    (net (code "85") (name "/SENSE7_6") (class "Default")
      (node (ref "CON2") (pin "31") (pinfunction "31_31") (pintype "passive"))
      (node (ref "SENSE7") (pin "2") (pinfunction "IO6_2") (pintype "bidirectional"))
    )
    (net (code "86") (name "/SENSE7_7") (class "Default")
      (node (ref "CON2") (pin "32") (pinfunction "32_32") (pintype "passive"))
      (node (ref "SENSE7") (pin "4") (pinfunction "IO7_4") (pintype "bidirectional"))
    )
    (net (code "87") (name "/SENSE7_OUT") (class "Default")
      (node (ref "SENSE21_1") (pin "13") (pinfunction "A1_13") (pintype "bidirectional"))
      (node (ref "SENSE7") (pin "3") (pinfunction "IO_3") (pintype "bidirectional"))
    )
    (net (code "88") (name "/SENSE_INHIBIT") (class "Default")
      (node (ref "JP4") (pin "9") (pinfunction "9_9") (pintype "passive"))
      (node (ref "SENSE0") (pin "6") (pinfunction "INH_6") (pintype "bidirectional"))
      (node (ref "SENSE1") (pin "6") (pinfunction "INH_6") (pintype "bidirectional"))
      (node (ref "SENSE2") (pin "6") (pinfunction "INH_6") (pintype "bidirectional"))
      (node (ref "SENSE21_0") (pin "6") (pinfunction "INH_6") (pintype "bidirectional"))
      (node (ref "SENSE21_1") (pin "6") (pinfunction "INH_6") (pintype "bidirectional"))
      (node (ref "SENSE3") (pin "6") (pinfunction "INH_6") (pintype "bidirectional"))
      (node (ref "SENSE4") (pin "6") (pinfunction "INH_6") (pintype "bidirectional"))
      (node (ref "SENSE5") (pin "6") (pinfunction "INH_6") (pintype "bidirectional"))
      (node (ref "SENSE6") (pin "6") (pinfunction "INH_6") (pintype "bidirectional"))
      (node (ref "SENSE7") (pin "6") (pinfunction "INH_6") (pintype "bidirectional"))
    )
    (net (code "89") (name "/SG0_OUT") (class "Default")
      (node (ref "JP1") (pin "1") (pinfunction "1_1") (pintype "passive"))
      (node (ref "SENSE21_0") (pin "14") (pinfunction "A_OUT_14") (pintype "bidirectional"))
    )
    (net (code "90") (name "/SG1_OUT") (class "Default")
      (node (ref "JP1") (pin "2") (pinfunction "2_2") (pintype "passive"))
      (node (ref "SENSE21_0") (pin "15") (pinfunction "B_OUT_15") (pintype "bidirectional"))
    )
    (net (code "91") (name "/SG2_OUT") (class "Default")
      (node (ref "JP1") (pin "3") (pinfunction "3_3") (pintype "passive"))
      (node (ref "SENSE21_0") (pin "4") (pinfunction "C_OUT_4") (pintype "bidirectional"))
    )
    (net (code "92") (name "/SG3_OUT") (class "Default")
      (node (ref "JP1") (pin "4") (pinfunction "4_4") (pintype "passive"))
      (node (ref "SENSE21_1") (pin "14") (pinfunction "A_OUT_14") (pintype "bidirectional"))
    )
    (net (code "93") (name "/TOGGLE_IN") (class "Default")
      (node (ref "JP2") (pin "1") (pinfunction "1_1") (pintype "passive"))
      (node (ref "JP2") (pin "2") (pinfunction "2_2") (pintype "passive"))
      (node (ref "R2") (pin "P$1") (pinfunction "1_P$1") (pintype "passive"))
    )
    (net (code "94") (name "/VDD") (class "Default")
      (node (ref "C1") (pin "2") (pinfunction "2_2") (pintype "passive"))
      (node (ref "C10") (pin "2") (pinfunction "2_2") (pintype "passive"))
      (node (ref "C2") (pin "2") (pinfunction "2_2") (pintype "passive"))
      (node (ref "C3") (pin "2") (pinfunction "2_2") (pintype "passive"))
      (node (ref "C4") (pin "2") (pinfunction "2_2") (pintype "passive"))
      (node (ref "C5") (pin "2") (pinfunction "2_2") (pintype "passive"))
      (node (ref "C6") (pin "2") (pinfunction "2_2") (pintype "passive"))
      (node (ref "C7") (pin "2") (pinfunction "2_2") (pintype "passive"))
      (node (ref "C8") (pin "2") (pinfunction "2_2") (pintype "passive"))
      (node (ref "C9") (pin "2") (pinfunction "2_2") (pintype "passive"))
      (node (ref "J1") (pin "3") (pinfunction "3_3") (pintype "passive"))
      (node (ref "JP4") (pin "1") (pinfunction "1_1") (pintype "passive"))
      (node (ref "K1") (pin "1") (pinfunction "DS1_1") (pintype "passive"))
      (node (ref "SENSE0") (pin "16") (pinfunction "VDD_16") (pintype "bidirectional"))
      (node (ref "SENSE1") (pin "16") (pinfunction "VDD_16") (pintype "bidirectional"))
      (node (ref "SENSE2") (pin "16") (pinfunction "VDD_16") (pintype "bidirectional"))
      (node (ref "SENSE21_0") (pin "16") (pinfunction "VDD_16") (pintype "bidirectional"))
      (node (ref "SENSE21_1") (pin "16") (pinfunction "VDD_16") (pintype "bidirectional"))
      (node (ref "SENSE3") (pin "16") (pinfunction "VDD_16") (pintype "bidirectional"))
      (node (ref "SENSE4") (pin "16") (pinfunction "VDD_16") (pintype "bidirectional"))
      (node (ref "SENSE5") (pin "16") (pinfunction "VDD_16") (pintype "bidirectional"))
      (node (ref "SENSE6") (pin "16") (pinfunction "VDD_16") (pintype "bidirectional"))
      (node (ref "SENSE7") (pin "16") (pinfunction "VDD_16") (pintype "bidirectional"))
    )
    (net (code "95") (name "/VDD2") (class "Default")
      (node (ref "C13") (pin "1") (pinfunction "+_1") (pintype "passive"))
      (node (ref "C14") (pin "1") (pinfunction "+_1") (pintype "passive"))
      (node (ref "C15") (pin "1") (pinfunction "+_1") (pintype "passive"))
      (node (ref "J1") (pin "5") (pinfunction "5_5") (pintype "passive"))
      (node (ref "JP3") (pin "1") (pinfunction "1_1") (pintype "passive"))
      (node (ref "JP3") (pin "3") (pinfunction "3_3") (pintype "passive"))
      (node (ref "JP3") (pin "5") (pinfunction "5_5") (pintype "passive"))
      (node (ref "JP3") (pin "7") (pinfunction "7_7") (pintype "passive"))
      (node (ref "JP3") (pin "9") (pinfunction "9_9") (pintype "passive"))
    )
    (net (code "96") (name "/VDD_33") (class "Default")
      (node (ref "JP1") (pin "5") (pinfunction "5_5") (pintype "passive"))
      (node (ref "R2") (pin "P$2") (pinfunction "2_P$2") (pintype "passive"))
      (node (ref "U$1") (pin "P5") (pinfunction "5_P5") (pintype "bidirectional"))
      (node (ref "U$3") (pin "P5") (pinfunction "5_P5") (pintype "bidirectional"))
    )
    (net (code "97") (name "unconnected-(CON1-Pad33)") (class "Default")
      (node (ref "CON1") (pin "33") (pinfunction "33_33") (pintype "passive"))
    )
    (net (code "98") (name "unconnected-(CON1-Pad34)") (class "Default")
      (node (ref "CON1") (pin "34") (pinfunction "34_34") (pintype "passive"))
    )
    (net (code "99") (name "unconnected-(CON2-Pad33)") (class "Default")
      (node (ref "CON2") (pin "33") (pinfunction "33_33") (pintype "passive"))
    )
    (net (code "100") (name "unconnected-(CON2-Pad34)") (class "Default")
      (node (ref "CON2") (pin "34") (pinfunction "34_34") (pintype "passive"))
    )
    (net (code "101") (name "unconnected-(JP1-Pad6)") (class "Default")
      (node (ref "JP1") (pin "6") (pinfunction "6_6") (pintype "passive"))
    )
    (net (code "102") (name "unconnected-(JP1-Pad7)") (class "Default")
      (node (ref "JP1") (pin "7") (pinfunction "7_7") (pintype "passive"))
    )
    (net (code "103") (name "unconnected-(JP4-Pad11)") (class "Default")
      (node (ref "JP4") (pin "11") (pinfunction "11_11") (pintype "passive"))
    )
    (net (code "104") (name "unconnected-(SENSE21_1-B_OUT-Pad15)") (class "Default")
      (node (ref "SENSE21_1") (pin "15") (pinfunction "B_OUT_15") (pintype "bidirectional"))
    )
    (net (code "105") (name "unconnected-(SENSE21_1-C_OUT-Pad4)") (class "Default")
      (node (ref "SENSE21_1") (pin "4") (pinfunction "C_OUT_4") (pintype "bidirectional"))
    )
    (net (code "106") (name "unconnected-(U$1-6-PadP6)") (class "Default")
      (node (ref "U$1") (pin "P6") (pinfunction "6_P6") (pintype "bidirectional"))
    )
    (net (code "107") (name "unconnected-(U$1-7-PadP7)") (class "Default")
      (node (ref "U$1") (pin "P7") (pinfunction "7_P7") (pintype "bidirectional"))
    )
    (net (code "108") (name "unconnected-(U$3-6-PadP6)") (class "Default")
      (node (ref "U$3") (pin "P6") (pinfunction "6_P6") (pintype "bidirectional"))
    )
    (net (code "109") (name "unconnected-(U$3-7-PadP7)") (class "Default")
      (node (ref "U$3") (pin "P7") (pinfunction "7_P7") (pintype "bidirectional"))
    )
  )
)
